# LAN8830_PINOUT.net
KiCad netlist of a schematic drawn in Altium Designer
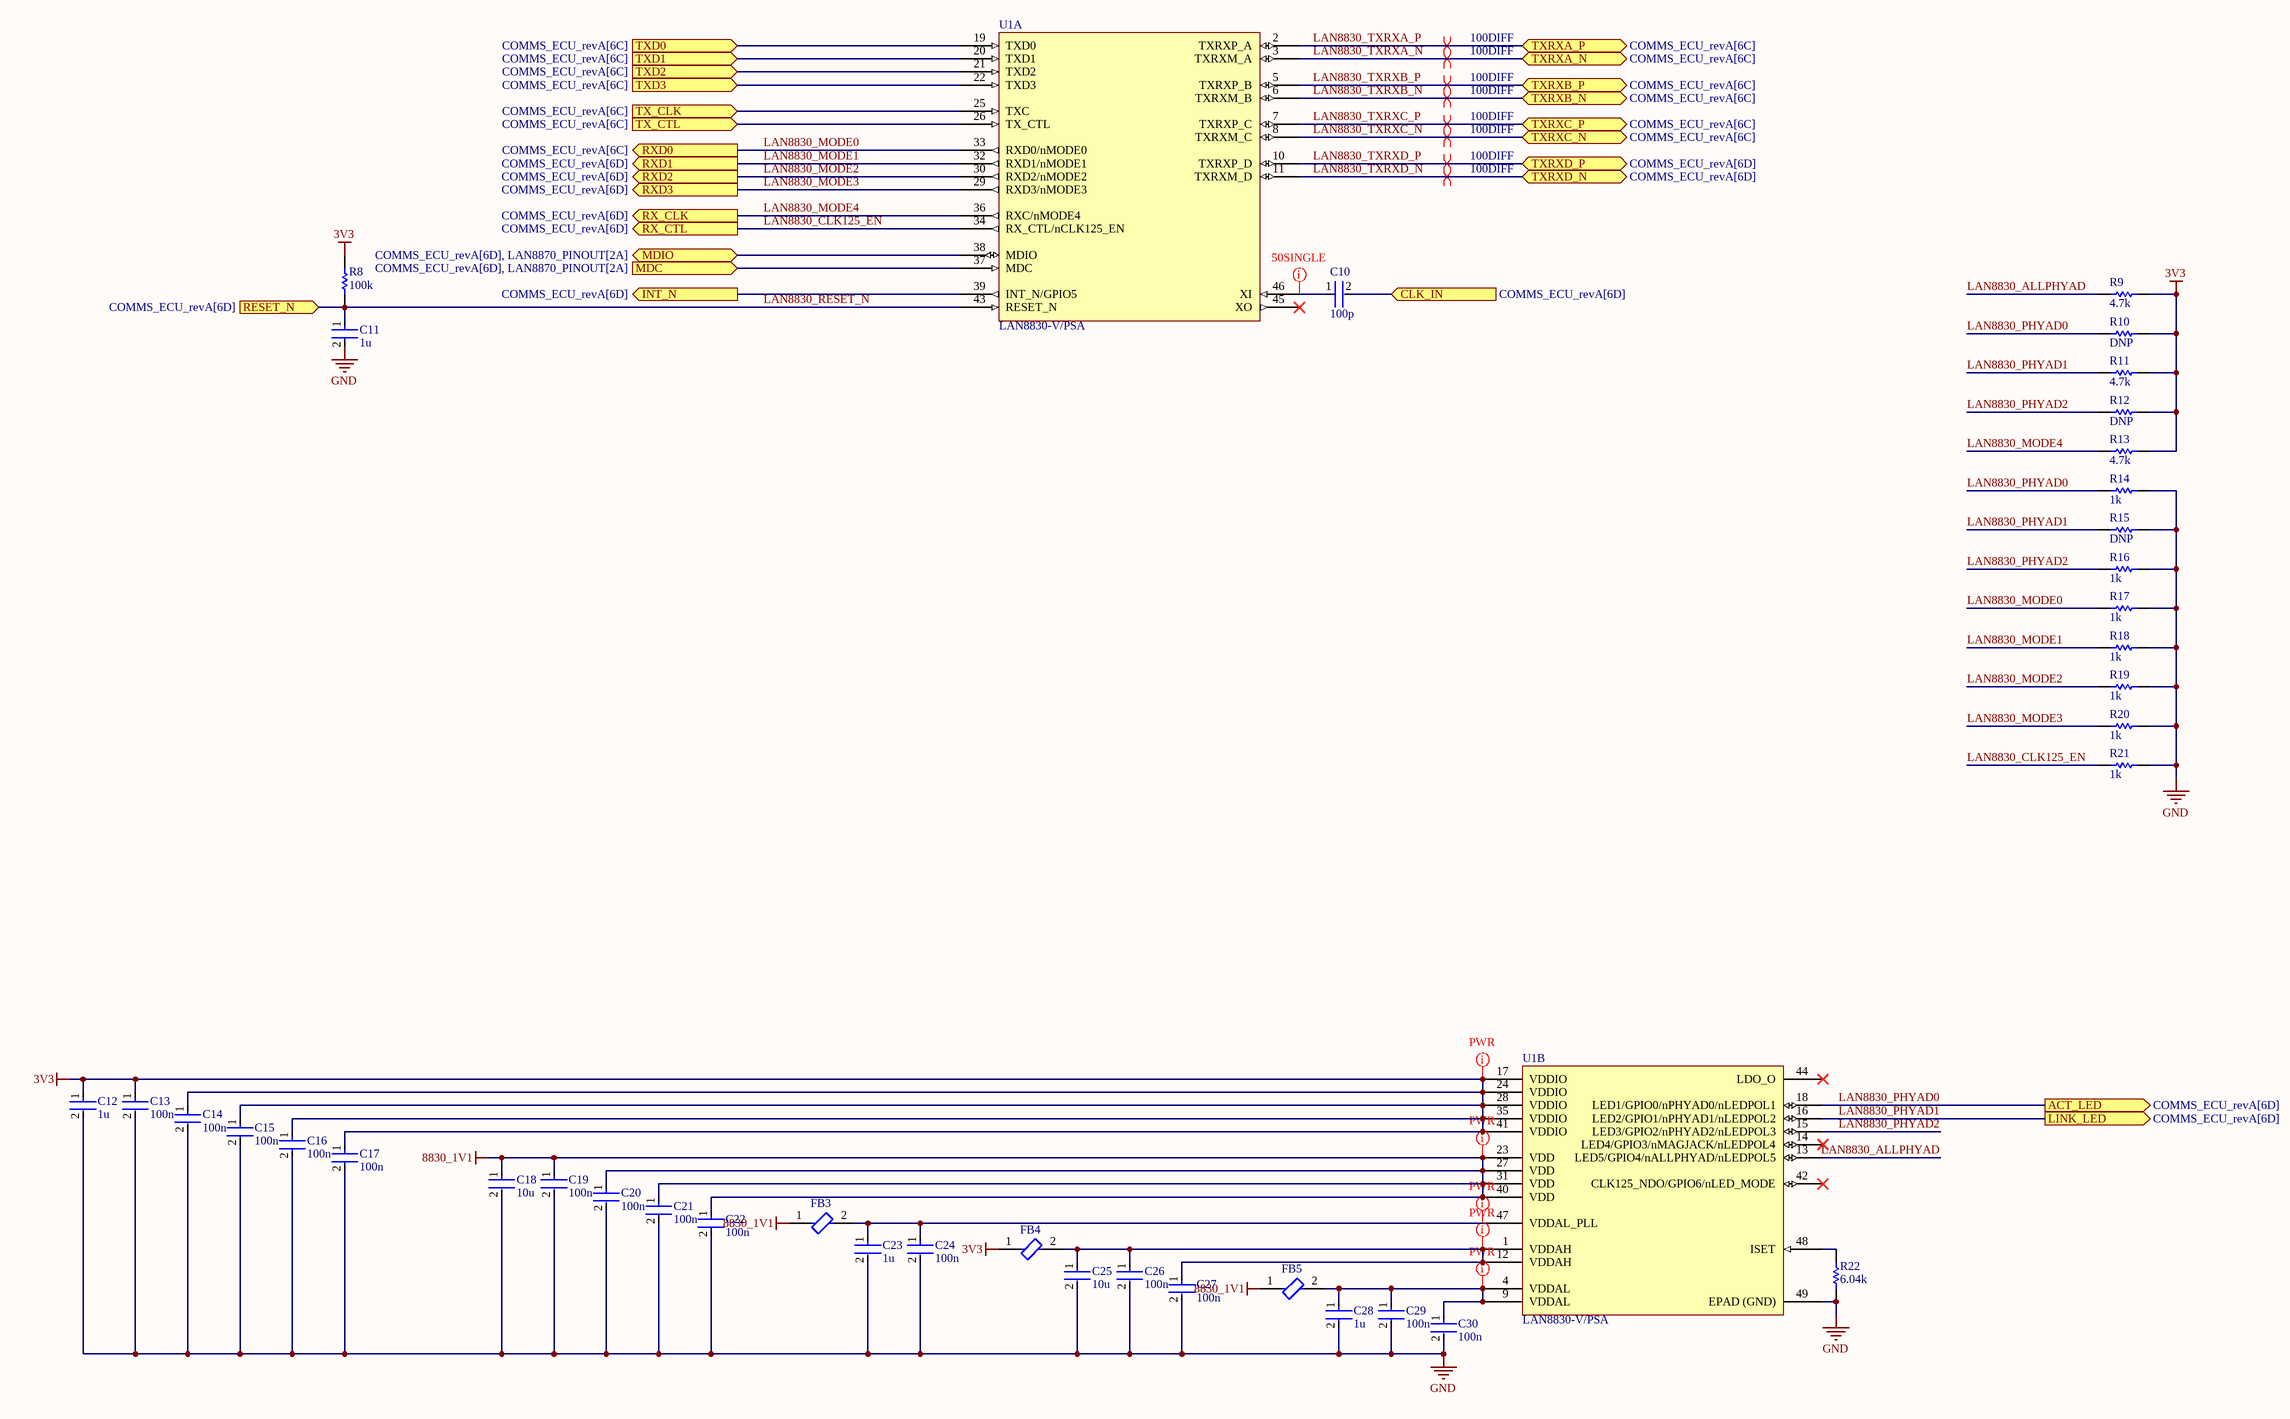
[diagram p0: LAN8830_PINOUT.SchDoc]

(export (version "E")
  (design (tool "Eeschema 10.0.6"))
  (components
    (comp (ref "C10")
      (value "100p")
      (footprint "FP-0402-L_1_0_0_05-W_0_5-IPC_A")
      (description "LARGE PADS, 0402 CAP, CHANGE COMMENT TO MATCH REAL P/N")
      (libsource (lib "Space Concordia") (part "b4654b650e69147ec39a6b967a45e02"))
    )
    (comp (ref "C11")
      (value "1u")
      (footprint "FP-0402-L_1_0_0_05-W_0_5-IPC_A")
      (description "LARGE PADS, 0402 CAP, CHANGE COMMENT TO MATCH REAL P/N")
      (libsource (lib "Space Concordia") (part "b4654b650e69147ec39a6b967a45e02"))
    )
    (comp (ref "C12")
      (value "1u")
      (footprint "FP-0402-L_1_0_0_05-W_0_5-IPC_A")
      (description "LARGE PADS, 0402 CAP, CHANGE COMMENT TO MATCH REAL P/N")
      (libsource (lib "Space Concordia") (part "b4654b650e69147ec39a6b967a45e02"))
    )
    (comp (ref "C13")
      (value "100n")
      (footprint "FP-0402-L_1_0_0_05-W_0_5-IPC_A")
      (description "LARGE PADS, 0402 CAP, CHANGE COMMENT TO MATCH REAL P/N")
      (libsource (lib "Space Concordia") (part "b4654b650e69147ec39a6b967a45e02"))
    )
    (comp (ref "C14")
      (value "100n")
      (footprint "FP-0402-L_1_0_0_05-W_0_5-IPC_A")
      (description "LARGE PADS, 0402 CAP, CHANGE COMMENT TO MATCH REAL P/N")
      (libsource (lib "Space Concordia") (part "b4654b650e69147ec39a6b967a45e02"))
    )
    (comp (ref "C15")
      (value "100n")
      (footprint "FP-0402-L_1_0_0_05-W_0_5-IPC_A")
      (description "LARGE PADS, 0402 CAP, CHANGE COMMENT TO MATCH REAL P/N")
      (libsource (lib "Space Concordia") (part "b4654b650e69147ec39a6b967a45e02"))
    )
    (comp (ref "C16")
      (value "100n")
      (footprint "FP-0402-L_1_0_0_05-W_0_5-IPC_A")
      (description "LARGE PADS, 0402 CAP, CHANGE COMMENT TO MATCH REAL P/N")
      (libsource (lib "Space Concordia") (part "b4654b650e69147ec39a6b967a45e02"))
    )
    (comp (ref "C17")
      (value "100n")
      (footprint "FP-0402-L_1_0_0_05-W_0_5-IPC_A")
      (description "LARGE PADS, 0402 CAP, CHANGE COMMENT TO MATCH REAL P/N")
      (libsource (lib "Space Concordia") (part "b4654b650e69147ec39a6b967a45e02"))
    )
    (comp (ref "C18")
      (value "10u")
      (footprint "FP-0402-L_1_0_0_05-W_0_5-IPC_A")
      (description "LARGE PADS, 0402 CAP, CHANGE COMMENT TO MATCH REAL P/N")
      (libsource (lib "Space Concordia") (part "b4654b650e69147ec39a6b967a45e02"))
    )
    (comp (ref "C19")
      (value "100n")
      (footprint "FP-0402-L_1_0_0_05-W_0_5-IPC_A")
      (description "LARGE PADS, 0402 CAP, CHANGE COMMENT TO MATCH REAL P/N")
      (libsource (lib "Space Concordia") (part "b4654b650e69147ec39a6b967a45e02"))
    )
    (comp (ref "C20")
      (value "100n")
      (footprint "FP-0402-L_1_0_0_05-W_0_5-IPC_A")
      (description "LARGE PADS, 0402 CAP, CHANGE COMMENT TO MATCH REAL P/N")
      (libsource (lib "Space Concordia") (part "b4654b650e69147ec39a6b967a45e02"))
    )
    (comp (ref "C21")
      (value "100n")
      (footprint "FP-0402-L_1_0_0_05-W_0_5-IPC_A")
      (description "LARGE PADS, 0402 CAP, CHANGE COMMENT TO MATCH REAL P/N")
      (libsource (lib "Space Concordia") (part "b4654b650e69147ec39a6b967a45e02"))
    )
    (comp (ref "C22")
      (value "100n")
      (footprint "FP-0402-L_1_0_0_05-W_0_5-IPC_A")
      (description "LARGE PADS, 0402 CAP, CHANGE COMMENT TO MATCH REAL P/N")
      (libsource (lib "Space Concordia") (part "b4654b650e69147ec39a6b967a45e02"))
    )
    (comp (ref "C23")
      (value "1u")
      (footprint "FP-0402-L_1_0_0_05-W_0_5-IPC_A")
      (description "LARGE PADS, 0402 CAP, CHANGE COMMENT TO MATCH REAL P/N")
      (libsource (lib "Space Concordia") (part "b4654b650e69147ec39a6b967a45e02"))
    )
    (comp (ref "C24")
      (value "100n")
      (footprint "FP-0402-L_1_0_0_05-W_0_5-IPC_A")
      (description "LARGE PADS, 0402 CAP, CHANGE COMMENT TO MATCH REAL P/N")
      (libsource (lib "Space Concordia") (part "b4654b650e69147ec39a6b967a45e02"))
    )
    (comp (ref "C25")
      (value "10u")
      (footprint "FP-0402-L_1_0_0_05-W_0_5-IPC_A")
      (description "LARGE PADS, 0402 CAP, CHANGE COMMENT TO MATCH REAL P/N")
      (libsource (lib "Space Concordia") (part "b4654b650e69147ec39a6b967a45e02"))
    )
    (comp (ref "C26")
      (value "100n")
      (footprint "FP-0402-L_1_0_0_05-W_0_5-IPC_A")
      (description "LARGE PADS, 0402 CAP, CHANGE COMMENT TO MATCH REAL P/N")
      (libsource (lib "Space Concordia") (part "b4654b650e69147ec39a6b967a45e02"))
    )
    (comp (ref "C27")
      (value "100n")
      (footprint "FP-0402-L_1_0_0_05-W_0_5-IPC_A")
      (description "LARGE PADS, 0402 CAP, CHANGE COMMENT TO MATCH REAL P/N")
      (libsource (lib "Space Concordia") (part "b4654b650e69147ec39a6b967a45e02"))
    )
    (comp (ref "C28")
      (value "1u")
      (footprint "FP-0402-L_1_0_0_05-W_0_5-IPC_A")
      (description "LARGE PADS, 0402 CAP, CHANGE COMMENT TO MATCH REAL P/N")
      (libsource (lib "Space Concordia") (part "b4654b650e69147ec39a6b967a45e02"))
    )
    (comp (ref "C29")
      (value "100n")
      (footprint "FP-0402-L_1_0_0_05-W_0_5-IPC_A")
      (description "LARGE PADS, 0402 CAP, CHANGE COMMENT TO MATCH REAL P/N")
      (libsource (lib "Space Concordia") (part "b4654b650e69147ec39a6b967a45e02"))
    )
    (comp (ref "C30")
      (value "100n")
      (footprint "FP-0402-L_1_0_0_05-W_0_5-IPC_A")
      (description "LARGE PADS, 0402 CAP, CHANGE COMMENT TO MATCH REAL P/N")
      (libsource (lib "Space Concordia") (part "b4654b650e69147ec39a6b967a45e02"))
    )
    (comp (ref "FB3")
      (value "BLM18KG331SH1D")
      (footprint "FP-BLM18-0_15-t0_8-IPC_B")
      (description "Chip Ferrite Bead, 0603, 330Ω @ 100MHz, 0.08Ω, 25%, 1.7A")
      (libsource (lib "Altium Content Vault") (part "5f30dd21d616792df468990f7003faa"))
    )
    (comp (ref "FB4")
      (value "BLM18KG331SH1D")
      (footprint "FP-BLM18-0_15-t0_8-IPC_B")
      (description "Chip Ferrite Bead, 0603, 330Ω @ 100MHz, 0.08Ω, 25%, 1.7A")
      (libsource (lib "Altium Content Vault") (part "5f30dd21d616792df468990f7003faa"))
    )
    (comp (ref "FB5")
      (value "BLM18KG331SH1D")
      (footprint "FP-BLM18-0_15-t0_8-IPC_B")
      (description "Chip Ferrite Bead, 0603, 330Ω @ 100MHz, 0.08Ω, 25%, 1.7A")
      (libsource (lib "Altium Content Vault") (part "5f30dd21d616792df468990f7003faa"))
    )
    (comp (ref "R8")
      (value "100k")
      (footprint "R0603B")
      (description "Resistor")
      (libsource (lib "Space Concordia") (part "Resistor"))
    )
    (comp (ref "R9")
      (value "4.7k")
      (footprint "R0603B")
      (description "Resistor")
      (libsource (lib "Space Concordia") (part "Resistor"))
    )
    (comp (ref "R10")
      (value "DNP")
      (footprint "R0603B")
      (description "Resistor")
      (libsource (lib "Space Concordia") (part "Resistor"))
    )
    (comp (ref "R11")
      (value "4.7k")
      (footprint "R0603B")
      (description "Resistor")
      (libsource (lib "Space Concordia") (part "Resistor"))
    )
    (comp (ref "R12")
      (value "DNP")
      (footprint "R0603B")
      (description "Resistor")
      (libsource (lib "Space Concordia") (part "Resistor"))
    )
    (comp (ref "R13")
      (value "4.7k")
      (footprint "R0603B")
      (description "Resistor")
      (libsource (lib "Space Concordia") (part "Resistor"))
    )
    (comp (ref "R14")
      (value "1k")
      (footprint "R0603B")
      (description "Resistor")
      (libsource (lib "Space Concordia") (part "Resistor"))
    )
    (comp (ref "R15")
      (value "DNP")
      (footprint "R0603B")
      (description "Resistor")
      (libsource (lib "Space Concordia") (part "Resistor"))
    )
    (comp (ref "R16")
      (value "1k")
      (footprint "R0603B")
      (description "Resistor")
      (libsource (lib "Space Concordia") (part "Resistor"))
    )
    (comp (ref "R17")
      (value "1k")
      (footprint "R0603B")
      (description "Resistor")
      (libsource (lib "Space Concordia") (part "Resistor"))
    )
    (comp (ref "R18")
      (value "1k")
      (footprint "R0603B")
      (description "Resistor")
      (libsource (lib "Space Concordia") (part "Resistor"))
    )
    (comp (ref "R19")
      (value "1k")
      (footprint "R0603B")
      (description "Resistor")
      (libsource (lib "Space Concordia") (part "Resistor"))
    )
    (comp (ref "R20")
      (value "1k")
      (footprint "R0603B")
      (description "Resistor")
      (libsource (lib "Space Concordia") (part "Resistor"))
    )
    (comp (ref "R21")
      (value "1k")
      (footprint "R0603B")
      (description "Resistor")
      (libsource (lib "Space Concordia") (part "Resistor"))
    )
    (comp (ref "R22")
      (value "6.04k")
      (footprint "R0603B")
      (description "Resistor")
      (libsource (lib "Space Concordia") (part "Resistor"))
    )
    (comp (ref "U1")
      (value "LAN8830-V/PSA")
      (footprint "QFN50P700X700X100_HS-49N")
      (description "LAN8830 Series RGMII Interface Gigabit Ethernet Transceiver - VQFN-48")
      (libsource (lib "Space Concordia") (part "LAN8830-V_PSA"))
    )
  )
  (nets
    (net (code "1") (name "/CLK_IN") (class "Default")
      (node (ref "C10") (pin "2") (pinfunction "2_2") (pintype "passive"))
    )
    (net (code "2") (name "/INT_N") (class "Default")
      (node (ref "U1") (pin "39") (pinfunction "INT_N/GPIO5_39") (pintype "output"))
    )
    (net (code "3") (name "/LAN8830_ALLPHYAD") (class "Default")
      (node (ref "R9") (pin "2") (pinfunction "2_2") (pintype "passive"))
      (node (ref "U1") (pin "13") (pinfunction "LED5/GPIO4/nALLPHYAD/nLEDPOL5_13") (pintype "bidirectional"))
    )
    (net (code "4") (name "/LAN8830_CLK125_EN") (class "Default")
      (node (ref "R21") (pin "2") (pinfunction "2_2") (pintype "passive"))
      (node (ref "U1") (pin "34") (pinfunction "RX_CTL/nCLK125_EN_34") (pintype "output"))
    )
    (net (code "5") (name "/LAN8830_MODE0") (class "Default")
      (node (ref "R17") (pin "2") (pinfunction "2_2") (pintype "passive"))
      (node (ref "U1") (pin "33") (pinfunction "RXD0/nMODE0_33") (pintype "output"))
    )
    (net (code "6") (name "/LAN8830_MODE1") (class "Default")
      (node (ref "R18") (pin "2") (pinfunction "2_2") (pintype "passive"))
      (node (ref "U1") (pin "32") (pinfunction "RXD1/nMODE1_32") (pintype "output"))
    )
    (net (code "7") (name "/LAN8830_MODE2") (class "Default")
      (node (ref "R19") (pin "2") (pinfunction "2_2") (pintype "passive"))
      (node (ref "U1") (pin "30") (pinfunction "RXD2/nMODE2_30") (pintype "output"))
    )
    (net (code "8") (name "/LAN8830_MODE3") (class "Default")
      (node (ref "R20") (pin "2") (pinfunction "2_2") (pintype "passive"))
      (node (ref "U1") (pin "29") (pinfunction "RXD3/nMODE3_29") (pintype "output"))
    )
    (net (code "9") (name "/LAN8830_MODE4") (class "Default")
      (node (ref "R13") (pin "2") (pinfunction "2_2") (pintype "passive"))
      (node (ref "U1") (pin "36") (pinfunction "RXC/nMODE4_36") (pintype "output"))
    )
    (net (code "10") (name "/LAN8830_PHYAD0") (class "Default")
      (node (ref "R10") (pin "1") (pinfunction "1_1") (pintype "passive"))
      (node (ref "R14") (pin "2") (pinfunction "2_2") (pintype "passive"))
      (node (ref "U1") (pin "18") (pinfunction "LED1/GPIO0/nPHYAD0/nLEDPOL1_18") (pintype "bidirectional"))
    )
    (net (code "11") (name "/LAN8830_PHYAD1") (class "Default")
      (node (ref "R11") (pin "2") (pinfunction "2_2") (pintype "passive"))
      (node (ref "R15") (pin "1") (pinfunction "1_1") (pintype "passive"))
      (node (ref "U1") (pin "16") (pinfunction "LED2/GPIO1/nPHYAD1/nLEDPOL2_16") (pintype "bidirectional"))
    )
    (net (code "12") (name "/LAN8830_PHYAD2") (class "Default")
      (node (ref "R12") (pin "1") (pinfunction "1_1") (pintype "passive"))
      (node (ref "R16") (pin "2") (pinfunction "2_2") (pintype "passive"))
      (node (ref "U1") (pin "15") (pinfunction "LED3/GPIO2/nPHYAD2/nLEDPOL3_15") (pintype "bidirectional"))
    )
    (net (code "13") (name "/LAN8830_RESET_N") (class "Default")
      (node (ref "C11") (pin "1") (pinfunction "1_1") (pintype "passive"))
      (node (ref "R8") (pin "2") (pinfunction "2_2") (pintype "passive"))
      (node (ref "U1") (pin "43") (pinfunction "RESET_N_43") (pintype "input"))
    )
    (net (code "14") (name "/LAN8830_TXRXA_N") (class "Default")
      (node (ref "U1") (pin "3") (pinfunction "TXRXM_A_3") (pintype "bidirectional"))
    )
    (net (code "15") (name "/LAN8830_TXRXA_P") (class "Default")
      (node (ref "U1") (pin "2") (pinfunction "TXRXP_A_2") (pintype "bidirectional"))
    )
    (net (code "16") (name "/LAN8830_TXRXB_N") (class "Default")
      (node (ref "U1") (pin "6") (pinfunction "TXRXM_B_6") (pintype "bidirectional"))
    )
    (net (code "17") (name "/LAN8830_TXRXB_P") (class "Default")
      (node (ref "U1") (pin "5") (pinfunction "TXRXP_B_5") (pintype "bidirectional"))
    )
    (net (code "18") (name "/LAN8830_TXRXC_N") (class "Default")
      (node (ref "U1") (pin "8") (pinfunction "TXRXM_C_8") (pintype "bidirectional"))
    )
    (net (code "19") (name "/LAN8830_TXRXC_P") (class "Default")
      (node (ref "U1") (pin "7") (pinfunction "TXRXP_C_7") (pintype "bidirectional"))
    )
    (net (code "20") (name "/LAN8830_TXRXD_N") (class "Default")
      (node (ref "U1") (pin "11") (pinfunction "TXRXM_D_11") (pintype "bidirectional"))
    )
    (net (code "21") (name "/LAN8830_TXRXD_P") (class "Default")
      (node (ref "U1") (pin "10") (pinfunction "TXRXP_D_10") (pintype "bidirectional"))
    )
    (net (code "22") (name "/MDC") (class "Default")
      (node (ref "U1") (pin "37") (pinfunction "MDC_37") (pintype "input"))
    )
    (net (code "23") (name "/MDIO") (class "Default")
      (node (ref "U1") (pin "38") (pinfunction "MDIO_38") (pintype "bidirectional"))
    )
    (net (code "24") (name "/TXD0") (class "Default")
      (node (ref "U1") (pin "19") (pinfunction "TXD0_19") (pintype "input"))
    )
    (net (code "25") (name "/TXD1") (class "Default")
      (node (ref "U1") (pin "20") (pinfunction "TXD1_20") (pintype "input"))
    )
    (net (code "26") (name "/TXD2") (class "Default")
      (node (ref "U1") (pin "21") (pinfunction "TXD2_21") (pintype "input"))
    )
    (net (code "27") (name "/TXD3") (class "Default")
      (node (ref "U1") (pin "22") (pinfunction "TXD3_22") (pintype "input"))
    )
    (net (code "28") (name "/TX_CLK") (class "Default")
      (node (ref "U1") (pin "25") (pinfunction "TXC_25") (pintype "input"))
    )
    (net (code "29") (name "/TX_CTL") (class "Default")
      (node (ref "U1") (pin "26") (pinfunction "TX_CTL_26") (pintype "input"))
    )
    (net (code "30") (name "3V3") (class "Default")
      (node (ref "C12") (pin "1") (pinfunction "1_1") (pintype "passive"))
      (node (ref "C13") (pin "1") (pinfunction "1_1") (pintype "passive"))
      (node (ref "C14") (pin "1") (pinfunction "1_1") (pintype "passive"))
      (node (ref "C15") (pin "1") (pinfunction "1_1") (pintype "passive"))
      (node (ref "C16") (pin "1") (pinfunction "1_1") (pintype "passive"))
      (node (ref "C17") (pin "1") (pinfunction "1_1") (pintype "passive"))
      (node (ref "FB4") (pin "1") (pinfunction "1_1") (pintype "passive"))
      (node (ref "R10") (pin "2") (pinfunction "2_2") (pintype "passive"))
      (node (ref "R11") (pin "1") (pinfunction "1_1") (pintype "passive"))
      (node (ref "R12") (pin "2") (pinfunction "2_2") (pintype "passive"))
      (node (ref "R13") (pin "1") (pinfunction "1_1") (pintype "passive"))
      (node (ref "R8") (pin "1") (pinfunction "1_1") (pintype "passive"))
      (node (ref "R9") (pin "1") (pinfunction "1_1") (pintype "passive"))
      (node (ref "U1") (pin "17") (pinfunction "VDDIO_17") (pintype "power_in"))
      (node (ref "U1") (pin "24") (pinfunction "VDDIO_24") (pintype "power_in"))
      (node (ref "U1") (pin "28") (pinfunction "VDDIO_28") (pintype "power_in"))
      (node (ref "U1") (pin "35") (pinfunction "VDDIO_35") (pintype "power_in"))
      (node (ref "U1") (pin "41") (pinfunction "VDDIO_41") (pintype "power_in"))
    )
    (net (code "31") (name "8830_1V1") (class "Default")
      (node (ref "C18") (pin "1") (pinfunction "1_1") (pintype "passive"))
      (node (ref "C19") (pin "1") (pinfunction "1_1") (pintype "passive"))
      (node (ref "C20") (pin "1") (pinfunction "1_1") (pintype "passive"))
      (node (ref "C21") (pin "1") (pinfunction "1_1") (pintype "passive"))
      (node (ref "C22") (pin "1") (pinfunction "1_1") (pintype "passive"))
      (node (ref "FB3") (pin "1") (pinfunction "1_1") (pintype "passive"))
      (node (ref "FB5") (pin "1") (pinfunction "1_1") (pintype "passive"))
      (node (ref "U1") (pin "23") (pinfunction "VDD_23") (pintype "power_in"))
      (node (ref "U1") (pin "27") (pinfunction "VDD_27") (pintype "power_in"))
      (node (ref "U1") (pin "31") (pinfunction "VDD_31") (pintype "power_in"))
      (node (ref "U1") (pin "40") (pinfunction "VDD_40") (pintype "power_in"))
    )
    (net (code "32") (name "GND") (class "Default")
      (node (ref "C11") (pin "2") (pinfunction "2_2") (pintype "passive"))
      (node (ref "C12") (pin "2") (pinfunction "2_2") (pintype "passive"))
      (node (ref "C13") (pin "2") (pinfunction "2_2") (pintype "passive"))
      (node (ref "C14") (pin "2") (pinfunction "2_2") (pintype "passive"))
      (node (ref "C15") (pin "2") (pinfunction "2_2") (pintype "passive"))
      (node (ref "C16") (pin "2") (pinfunction "2_2") (pintype "passive"))
      (node (ref "C17") (pin "2") (pinfunction "2_2") (pintype "passive"))
      (node (ref "C18") (pin "2") (pinfunction "2_2") (pintype "passive"))
      (node (ref "C19") (pin "2") (pinfunction "2_2") (pintype "passive"))
      (node (ref "C20") (pin "2") (pinfunction "2_2") (pintype "passive"))
      (node (ref "C21") (pin "2") (pinfunction "2_2") (pintype "passive"))
      (node (ref "C22") (pin "2") (pinfunction "2_2") (pintype "passive"))
      (node (ref "C23") (pin "2") (pinfunction "2_2") (pintype "passive"))
      (node (ref "C24") (pin "2") (pinfunction "2_2") (pintype "passive"))
      (node (ref "C25") (pin "2") (pinfunction "2_2") (pintype "passive"))
      (node (ref "C26") (pin "2") (pinfunction "2_2") (pintype "passive"))
      (node (ref "C27") (pin "2") (pinfunction "2_2") (pintype "passive"))
      (node (ref "C28") (pin "2") (pinfunction "2_2") (pintype "passive"))
      (node (ref "C29") (pin "2") (pinfunction "2_2") (pintype "passive"))
      (node (ref "C30") (pin "2") (pinfunction "2_2") (pintype "passive"))
      (node (ref "R14") (pin "1") (pinfunction "1_1") (pintype "passive"))
      (node (ref "R15") (pin "2") (pinfunction "2_2") (pintype "passive"))
      (node (ref "R16") (pin "1") (pinfunction "1_1") (pintype "passive"))
      (node (ref "R17") (pin "1") (pinfunction "1_1") (pintype "passive"))
      (node (ref "R18") (pin "1") (pinfunction "1_1") (pintype "passive"))
      (node (ref "R19") (pin "1") (pinfunction "1_1") (pintype "passive"))
      (node (ref "R20") (pin "1") (pinfunction "1_1") (pintype "passive"))
      (node (ref "R21") (pin "1") (pinfunction "1_1") (pintype "passive"))
      (node (ref "R22") (pin "2") (pinfunction "2_2") (pintype "passive"))
      (node (ref "U1") (pin "49") (pinfunction "EPAD_(GND)_49") (pintype "power_in"))
    )
    (net (code "33") (name "Net-(C25-Pad1)") (class "Default")
      (node (ref "C25") (pin "1") (pinfunction "1_1") (pintype "passive"))
      (node (ref "C26") (pin "1") (pinfunction "1_1") (pintype "passive"))
      (node (ref "C27") (pin "1") (pinfunction "1_1") (pintype "passive"))
      (node (ref "FB4") (pin "2") (pinfunction "2_2") (pintype "passive"))
      (node (ref "U1") (pin "1") (pinfunction "VDDAH_1") (pintype "power_in"))
      (node (ref "U1") (pin "12") (pinfunction "VDDAH_12") (pintype "power_in"))
    )
    (net (code "34") (name "Net-(C28-Pad1)") (class "Default")
      (node (ref "C28") (pin "1") (pinfunction "1_1") (pintype "passive"))
      (node (ref "C29") (pin "1") (pinfunction "1_1") (pintype "passive"))
      (node (ref "C30") (pin "1") (pinfunction "1_1") (pintype "passive"))
      (node (ref "FB5") (pin "2") (pinfunction "2_2") (pintype "passive"))
      (node (ref "U1") (pin "4") (pinfunction "VDDAL_4") (pintype "power_in"))
      (node (ref "U1") (pin "9") (pinfunction "VDDAL_9") (pintype "power_in"))
    )
    (net (code "35") (name "Net-(U1A-XI)") (class "Default")
      (node (ref "C10") (pin "1") (pinfunction "1_1") (pintype "passive"))
      (node (ref "U1") (pin "46") (pinfunction "XI_46") (pintype "input"))
    )
    (net (code "36") (name "Net-(U1B-ISET)") (class "Default")
      (node (ref "R22") (pin "1") (pinfunction "1_1") (pintype "passive"))
      (node (ref "U1") (pin "48") (pinfunction "ISET_48") (pintype "input"))
    )
    (net (code "37") (name "Net-(U1B-VDDAL_PLL)") (class "Default")
      (node (ref "C23") (pin "1") (pinfunction "1_1") (pintype "passive"))
      (node (ref "C24") (pin "1") (pinfunction "1_1") (pintype "passive"))
      (node (ref "FB3") (pin "2") (pinfunction "2_2") (pintype "passive"))
      (node (ref "U1") (pin "47") (pinfunction "VDDAL_PLL_47") (pintype "power_in"))
    )
    (net (code "38") (name "unconnected-(U1A-XO-Pad45)") (class "Default")
      (node (ref "U1") (pin "45") (pinfunction "XO_45") (pintype "output+no_connect"))
    )
    (net (code "39") (name "unconnected-(U1B-CLK125_NDO{slash}GPIO6{slash}nLED_MODE-Pad42)") (class "Default")
      (node (ref "U1") (pin "42") (pinfunction "CLK125_NDO/GPIO6/nLED_MODE_42") (pintype "bidirectional+no_connect"))
    )
    (net (code "40") (name "unconnected-(U1B-LDO_O-Pad44)") (class "Default")
      (node (ref "U1") (pin "44") (pinfunction "LDO_O_44") (pintype "power_in+no_connect"))
    )
    (net (code "41") (name "unconnected-(U1B-LED4{slash}GPIO3{slash}nMAGJACK{slash}nLEDPOL4-Pad14)") (class "Default")
      (node (ref "U1") (pin "14") (pinfunction "LED4/GPIO3/nMAGJACK/nLEDPOL4_14") (pintype "bidirectional+no_connect"))
    )
  )
)
